# A_shield.net
KiCad netlist of a schematic drawn in EAGLE
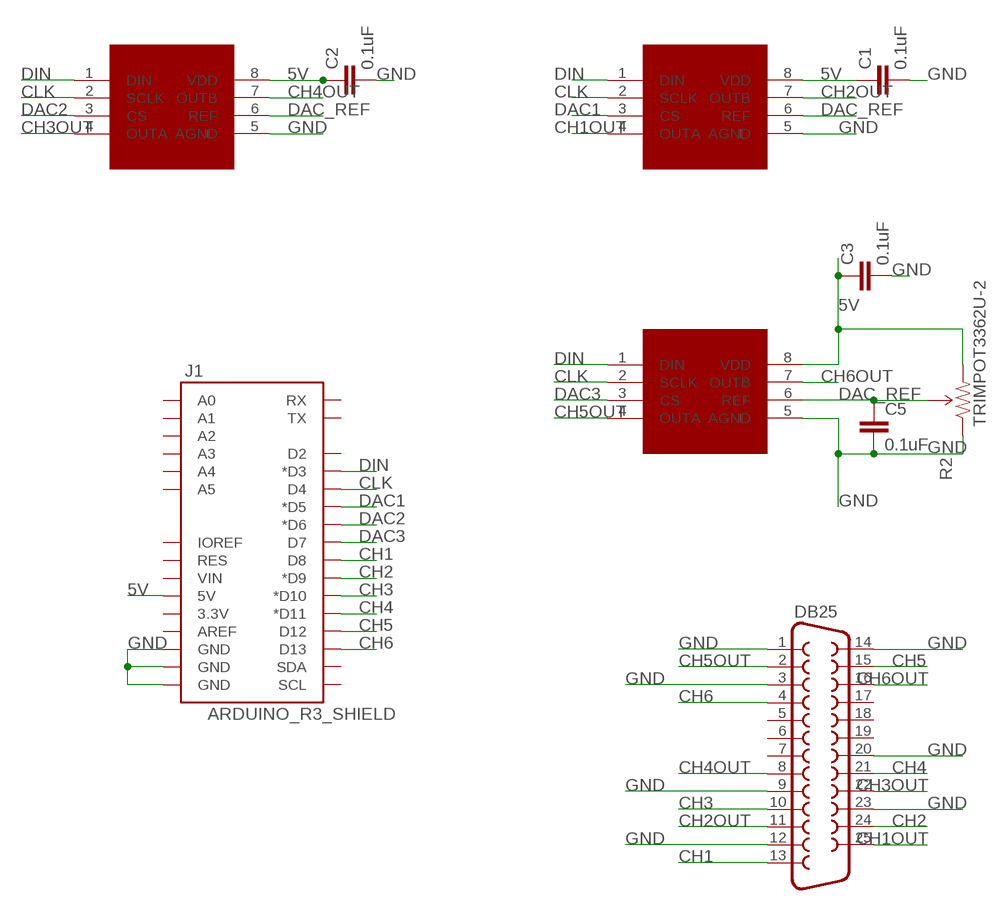
[diagram p0: schematic, sheet 1]

(export (version "E")
  (design (tool "Eeschema 10.0.6"))
  (components
    (comp (ref "C1")
      (value "0.1uF")
      (footprint "eagle-import:1206")
      (libsource (lib "eagle-import") (part "CAP1206"))
    )
    (comp (ref "C2")
      (value "0.1uF")
      (footprint "eagle-import:1206")
      (libsource (lib "eagle-import") (part "CAP1206"))
    )
    (comp (ref "C3")
      (value "0.1uF")
      (footprint "eagle-import:1206")
      (libsource (lib "eagle-import") (part "CAP1206"))
    )
    (comp (ref "C5")
      (value "0.1uF")
      (footprint "eagle-import:1206")
      (libsource (lib "eagle-import") (part "CAP1206"))
    )
    (comp (ref "DAC1")
      (value "TLV5618")
      (footprint "eagle-import:DIL08")
      (libsource (lib "eagle-import") (part "TLV5618"))
    )
    (comp (ref "DAC2")
      (value "TLV5618")
      (footprint "eagle-import:DIL08")
      (libsource (lib "eagle-import") (part "TLV5618"))
    )
    (comp (ref "DAC3")
      (value "TLV5618")
      (footprint "eagle-import:DIL08")
      (libsource (lib "eagle-import") (part "TLV5618"))
    )
    (comp (ref "DB25")
      (value "F25HP")
      (footprint "eagle-import:F25HP")
      (libsource (lib "eagle-import") (part "F25HP"))
    )
    (comp (ref "J1")
      (value "ARDUINO_R3_SHIELD")
      (footprint "eagle-import:UNO_R3_SHIELD")
      (libsource (lib "eagle-import") (part "ARDUINO_R3_SHIELD"))
    )
    (comp (ref "R2")
      (value "TRIMPOT3362U-2")
      (footprint "eagle-import:3362U-2")
      (libsource (lib "eagle-import") (part "TRIMPOT3362U-2"))
    )
  )
  (nets
    (net (code "1") (name "/5V") (class "Default")
      (node (ref "C1") (pin "1") (pinfunction "1_1") (pintype "passive"))
      (node (ref "C2") (pin "1") (pinfunction "1_1") (pintype "passive"))
      (node (ref "C3") (pin "1") (pinfunction "1_1") (pintype "passive"))
      (node (ref "DAC1") (pin "8") (pinfunction "VDD_8") (pintype "bidirectional"))
      (node (ref "DAC2") (pin "8") (pinfunction "VDD_8") (pintype "bidirectional"))
      (node (ref "DAC3") (pin "8") (pinfunction "VDD_8") (pintype "bidirectional"))
      (node (ref "J1") (pin "5V") (pinfunction "5V_5V") (pintype "bidirectional"))
      (node (ref "R2") (pin "3") (pinfunction "CW_3") (pintype "passive"))
    )
    (net (code "2") (name "/CH1") (class "Default")
      (node (ref "DB25") (pin "13") (pinfunction "13_13") (pintype "passive"))
      (node (ref "J1") (pin "D8") (pinfunction "D8_D8") (pintype "bidirectional"))
    )
    (net (code "3") (name "/CH1OUT") (class "Default")
      (node (ref "DAC1") (pin "4") (pinfunction "OUTA_4") (pintype "bidirectional"))
      (node (ref "DB25") (pin "25") (pinfunction "25_25") (pintype "passive"))
    )
    (net (code "4") (name "/CH2") (class "Default")
      (node (ref "DB25") (pin "24") (pinfunction "24_24") (pintype "passive"))
      (node (ref "J1") (pin "D9") (pinfunction "*D9_D9") (pintype "bidirectional"))
    )
    (net (code "5") (name "/CH2OUT") (class "Default")
      (node (ref "DAC1") (pin "7") (pinfunction "OUTB_7") (pintype "bidirectional"))
      (node (ref "DB25") (pin "11") (pinfunction "11_11") (pintype "passive"))
    )
    (net (code "6") (name "/CH3") (class "Default")
      (node (ref "DB25") (pin "10") (pinfunction "10_10") (pintype "passive"))
      (node (ref "J1") (pin "D10") (pinfunction "*D10_D10") (pintype "bidirectional"))
    )
    (net (code "7") (name "/CH3OUT") (class "Default")
      (node (ref "DAC3") (pin "4") (pinfunction "OUTA_4") (pintype "bidirectional"))
      (node (ref "DB25") (pin "22") (pinfunction "22_22") (pintype "passive"))
    )
    (net (code "8") (name "/CH4") (class "Default")
      (node (ref "DB25") (pin "21") (pinfunction "21_21") (pintype "passive"))
      (node (ref "J1") (pin "D11") (pinfunction "*D11_D11") (pintype "bidirectional"))
    )
    (net (code "9") (name "/CH4OUT") (class "Default")
      (node (ref "DAC3") (pin "7") (pinfunction "OUTB_7") (pintype "bidirectional"))
      (node (ref "DB25") (pin "8") (pinfunction "8_8") (pintype "passive"))
    )
    (net (code "10") (name "/CH5") (class "Default")
      (node (ref "DB25") (pin "15") (pinfunction "15_15") (pintype "passive"))
      (node (ref "J1") (pin "D12") (pinfunction "D12_D12") (pintype "bidirectional"))
    )
    (net (code "11") (name "/CH5OUT") (class "Default")
      (node (ref "DAC2") (pin "4") (pinfunction "OUTA_4") (pintype "bidirectional"))
      (node (ref "DB25") (pin "2") (pinfunction "2_2") (pintype "passive"))
    )
    (net (code "12") (name "/CH6") (class "Default")
      (node (ref "DB25") (pin "4") (pinfunction "4_4") (pintype "passive"))
      (node (ref "J1") (pin "D13") (pinfunction "D13_D13") (pintype "bidirectional"))
    )
    (net (code "13") (name "/CH6OUT") (class "Default")
      (node (ref "DAC2") (pin "7") (pinfunction "OUTB_7") (pintype "bidirectional"))
      (node (ref "DB25") (pin "16") (pinfunction "16_16") (pintype "passive"))
    )
    (net (code "14") (name "/CLK") (class "Default")
      (node (ref "DAC1") (pin "2") (pinfunction "SCLK_2") (pintype "bidirectional"))
      (node (ref "DAC2") (pin "2") (pinfunction "SCLK_2") (pintype "bidirectional"))
      (node (ref "DAC3") (pin "2") (pinfunction "SCLK_2") (pintype "bidirectional"))
      (node (ref "J1") (pin "D4") (pinfunction "D4_D4") (pintype "bidirectional"))
    )
    (net (code "15") (name "/DAC1") (class "Default")
      (node (ref "DAC1") (pin "3") (pinfunction "CS_3") (pintype "bidirectional"))
      (node (ref "J1") (pin "D5") (pinfunction "*D5_D5") (pintype "bidirectional"))
    )
    (net (code "16") (name "/DAC2") (class "Default")
      (node (ref "DAC3") (pin "3") (pinfunction "CS_3") (pintype "bidirectional"))
      (node (ref "J1") (pin "D6") (pinfunction "*D6_D6") (pintype "bidirectional"))
    )
    (net (code "17") (name "/DAC3") (class "Default")
      (node (ref "DAC2") (pin "3") (pinfunction "CS_3") (pintype "bidirectional"))
      (node (ref "J1") (pin "D7") (pinfunction "D7_D7") (pintype "bidirectional"))
    )
    (net (code "18") (name "/DAC_REF") (class "Default")
      (node (ref "C5") (pin "1") (pinfunction "1_1") (pintype "passive"))
      (node (ref "DAC1") (pin "6") (pinfunction "REF_6") (pintype "bidirectional"))
      (node (ref "DAC2") (pin "6") (pinfunction "REF_6") (pintype "bidirectional"))
      (node (ref "DAC3") (pin "6") (pinfunction "REF_6") (pintype "bidirectional"))
      (node (ref "R2") (pin "2") (pinfunction "WIPER_2") (pintype "passive"))
    )
    (net (code "19") (name "/DIN") (class "Default")
      (node (ref "DAC1") (pin "1") (pinfunction "DIN_1") (pintype "bidirectional"))
      (node (ref "DAC2") (pin "1") (pinfunction "DIN_1") (pintype "bidirectional"))
      (node (ref "DAC3") (pin "1") (pinfunction "DIN_1") (pintype "bidirectional"))
      (node (ref "J1") (pin "D3") (pinfunction "*D3_D3") (pintype "bidirectional"))
    )
    (net (code "20") (name "/GND") (class "Default")
      (node (ref "C1") (pin "2") (pinfunction "2_2") (pintype "passive"))
      (node (ref "C2") (pin "2") (pinfunction "2_2") (pintype "passive"))
      (node (ref "C3") (pin "2") (pinfunction "2_2") (pintype "passive"))
      (node (ref "C5") (pin "2") (pinfunction "2_2") (pintype "passive"))
      (node (ref "DAC1") (pin "5") (pinfunction "AGND_5") (pintype "bidirectional"))
      (node (ref "DAC2") (pin "5") (pinfunction "AGND_5") (pintype "bidirectional"))
      (node (ref "DAC3") (pin "5") (pinfunction "AGND_5") (pintype "bidirectional"))
      (node (ref "DB25") (pin "1") (pinfunction "1_1") (pintype "passive"))
      (node (ref "DB25") (pin "12") (pinfunction "12_12") (pintype "passive"))
      (node (ref "DB25") (pin "14") (pinfunction "14_14") (pintype "passive"))
      (node (ref "DB25") (pin "20") (pinfunction "20_20") (pintype "passive"))
      (node (ref "DB25") (pin "23") (pinfunction "23_23") (pintype "passive"))
      (node (ref "DB25") (pin "3") (pinfunction "3_3") (pintype "passive"))
      (node (ref "DB25") (pin "9") (pinfunction "9_9") (pintype "passive"))
      (node (ref "J1") (pin "GND@0") (pinfunction "GND_GND@0") (pintype "bidirectional"))
      (node (ref "J1") (pin "GND@1") (pinfunction "GND_GND@1") (pintype "bidirectional"))
      (node (ref "J1") (pin "GND@2") (pinfunction "GND_GND@2") (pintype "bidirectional"))
      (node (ref "R2") (pin "1") (pinfunction "CCW_1") (pintype "passive"))
    )
    (net (code "21") (name "unconnected-(DB25-Pad5)") (class "Default")
      (node (ref "DB25") (pin "5") (pinfunction "5_5") (pintype "passive"))
    )
    (net (code "22") (name "unconnected-(DB25-Pad6)") (class "Default")
      (node (ref "DB25") (pin "6") (pinfunction "6_6") (pintype "passive"))
    )
    (net (code "23") (name "unconnected-(DB25-Pad7)") (class "Default")
      (node (ref "DB25") (pin "7") (pinfunction "7_7") (pintype "passive"))
    )
    (net (code "24") (name "unconnected-(DB25-Pad17)") (class "Default")
      (node (ref "DB25") (pin "17") (pinfunction "17_17") (pintype "passive"))
    )
    (net (code "25") (name "unconnected-(DB25-Pad18)") (class "Default")
      (node (ref "DB25") (pin "18") (pinfunction "18_18") (pintype "passive"))
    )
    (net (code "26") (name "unconnected-(DB25-Pad19)") (class "Default")
      (node (ref "DB25") (pin "19") (pinfunction "19_19") (pintype "passive"))
    )
    (net (code "27") (name "unconnected-(J1-Pad3.3V)") (class "Default")
      (node (ref "J1") (pin "3.3V") (pinfunction "3.3V_3.3V") (pintype "bidirectional"))
    )
    (net (code "28") (name "unconnected-(J1-PadA0)") (class "Default")
      (node (ref "J1") (pin "A0") (pinfunction "A0_A0") (pintype "bidirectional"))
    )
    (net (code "29") (name "unconnected-(J1-PadA1)") (class "Default")
      (node (ref "J1") (pin "A1") (pinfunction "A1_A1") (pintype "bidirectional"))
    )
    (net (code "30") (name "unconnected-(J1-PadA2)") (class "Default")
      (node (ref "J1") (pin "A2") (pinfunction "A2_A2") (pintype "bidirectional"))
    )
    (net (code "31") (name "unconnected-(J1-PadA3)") (class "Default")
      (node (ref "J1") (pin "A3") (pinfunction "A3_A3") (pintype "bidirectional"))
    )
    (net (code "32") (name "unconnected-(J1-PadA4)") (class "Default")
      (node (ref "J1") (pin "A4") (pinfunction "A4_A4") (pintype "bidirectional"))
    )
    (net (code "33") (name "unconnected-(J1-PadA5)") (class "Default")
      (node (ref "J1") (pin "A5") (pinfunction "A5_A5") (pintype "bidirectional"))
    )
    (net (code "34") (name "unconnected-(J1-PadAREF)") (class "Default")
      (node (ref "J1") (pin "AREF") (pinfunction "AREF_AREF") (pintype "bidirectional"))
    )
    (net (code "35") (name "unconnected-(J1-PadD2)") (class "Default")
      (node (ref "J1") (pin "D2") (pinfunction "D2_D2") (pintype "bidirectional"))
    )
    (net (code "36") (name "unconnected-(J1-PadIOREF)") (class "Default")
      (node (ref "J1") (pin "IOREF") (pinfunction "IOREF_IOREF") (pintype "bidirectional"))
    )
    (net (code "37") (name "unconnected-(J1-PadRES)") (class "Default")
      (node (ref "J1") (pin "RES") (pinfunction "RES_RES") (pintype "bidirectional"))
    )
    (net (code "38") (name "unconnected-(J1-PadRX)") (class "Default")
      (node (ref "J1") (pin "RX") (pinfunction "RX_RX") (pintype "bidirectional"))
    )
    (net (code "39") (name "unconnected-(J1-PadSCL)") (class "Default")
      (node (ref "J1") (pin "SCL") (pinfunction "SCL_SCL") (pintype "bidirectional"))
    )
    (net (code "40") (name "unconnected-(J1-PadSDA)") (class "Default")
      (node (ref "J1") (pin "SDA") (pinfunction "SDA_SDA") (pintype "bidirectional"))
    )
    (net (code "41") (name "unconnected-(J1-PadTX)") (class "Default")
      (node (ref "J1") (pin "TX") (pinfunction "TX_TX") (pintype "bidirectional"))
    )
    (net (code "42") (name "unconnected-(J1-PadVIN)") (class "Default")
      (node (ref "J1") (pin "VIN") (pinfunction "VIN_VIN") (pintype "bidirectional"))
    )
  )
)
